# Debugger.net
KiCad netlist of a schematic drawn in Altium Designer
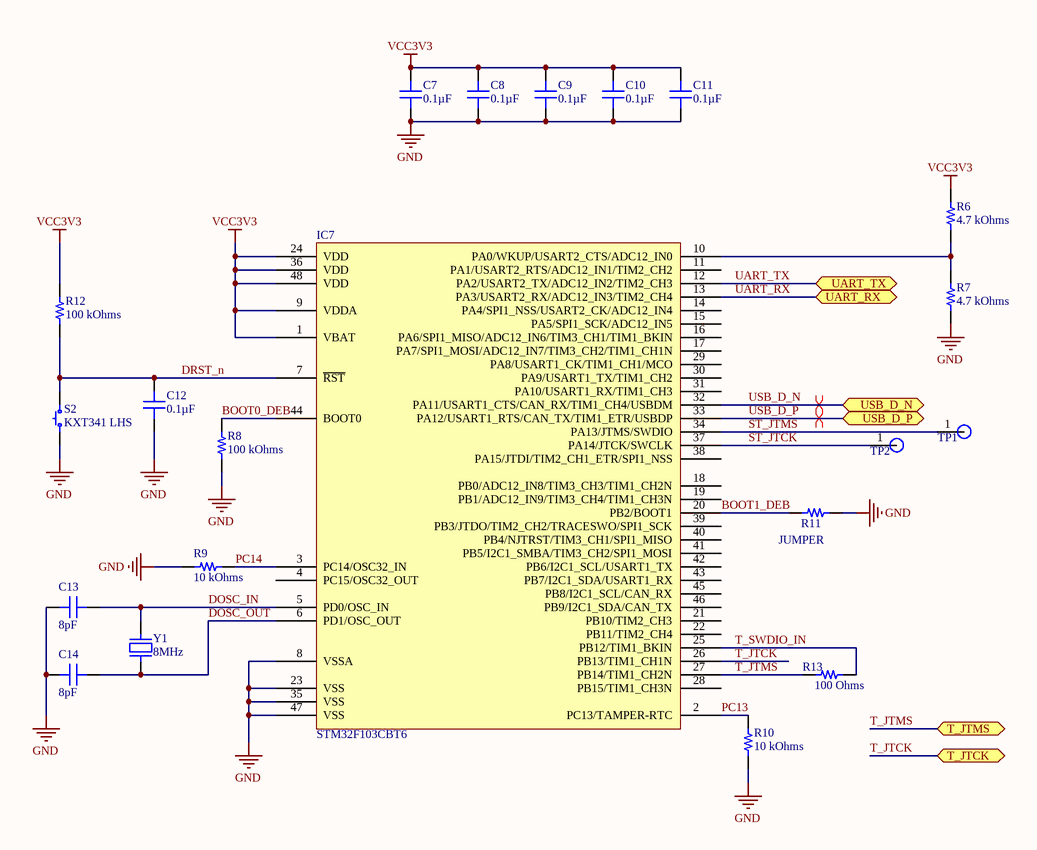
[diagram p0: Debugger.SchDoc]

(export (version "E")
  (design (tool "Eeschema 10.0.6"))
  (components
    (comp (ref "C7")
      (value "0.1µF")
      (footprint "CAP 0201_0603")
      (description "CAP CER 0.1UF 16V X5R 0201")
      (fields (field (name "PART NUMBER") "EMK063BJ104KP-F") (field (name "MANUFACTURER") "Taiyo Yuden"))
      (libsource (lib "Celestial") (part "Capacitor"))
    )
    (comp (ref "C8")
      (value "0.1µF")
      (footprint "CAP 0201_0603")
      (description "CAP CER 0.1UF 16V X5R 0201")
      (fields (field (name "PART NUMBER") "EMK063BJ104KP-F") (field (name "MANUFACTURER") "Taiyo Yuden"))
      (libsource (lib "Celestial") (part "Capacitor"))
    )
    (comp (ref "C9")
      (value "0.1µF")
      (footprint "CAP 0201_0603")
      (description "CAP CER 0.1UF 16V X5R 0201")
      (fields (field (name "PART NUMBER") "EMK063BJ104KP-F") (field (name "MANUFACTURER") "Taiyo Yuden"))
      (libsource (lib "Celestial") (part "Capacitor"))
    )
    (comp (ref "C10")
      (value "0.1µF")
      (footprint "CAP 0201_0603")
      (description "CAP CER 0.1UF 16V X5R 0201")
      (fields (field (name "PART NUMBER") "EMK063BJ104KP-F") (field (name "MANUFACTURER") "Taiyo Yuden"))
      (libsource (lib "Celestial") (part "Capacitor"))
    )
    (comp (ref "C11")
      (value "0.1µF")
      (footprint "CAP 0201_0603")
      (description "CAP CER 0.1UF 16V X5R 0201")
      (fields (field (name "PART NUMBER") "EMK063BJ104KP-F") (field (name "MANUFACTURER") "Taiyo Yuden"))
      (libsource (lib "Celestial") (part "Capacitor"))
    )
    (comp (ref "C12")
      (value "0.1µF")
      (footprint "CAP 0201_0603")
      (description "CAP CER 0.1UF 16V X5R 0201")
      (fields (field (name "PART NUMBER") "EMK063BJ104KP-F") (field (name "MANUFACTURER") "Taiyo Yuden"))
      (libsource (lib "Celestial") (part "Capacitor"))
    )
    (comp (ref "C13")
      (value "8pF")
      (footprint "CAP 0402_1005")
      (description "CAP CER 8PF 50V NP0 0402")
      (fields
        (field (name "PART NUMBER") "C1005NP01H080D050BA")
        (field (name "MANUFACTURER") "TDK Corporation")
      )
      (libsource (lib "Celestial") (part "Capacitor"))
    )
    (comp (ref "C14")
      (value "8pF")
      (footprint "CAP 0402_1005")
      (description "CAP CER 8PF 50V NP0 0402")
      (fields
        (field (name "PART NUMBER") "C1005NP01H080D050BA")
        (field (name "MANUFACTURER") "TDK Corporation")
      )
      (libsource (lib "Celestial") (part "Capacitor"))
    )
    (comp (ref "IC7")
      (value "STM32F103CBT6")
      (footprint "ST LQFP-48 7X7MM")
      (description "IC MCU 32BIT 128KB FLASH 48LQFP")
      (fields (field (name "MANUFACTURER") "STMicroelectronics"))
      (libsource (lib "Celestial") (part "ST STM32F103 48PIN"))
    )
    (comp (ref "R6")
      (value "4.7 kOhms")
      (footprint "RES 0201_0603")
      (description "RES SMD 4.7K OHM 1% 1/20W 0201")
      (fields (field (name "PART NUMBER") "CRCW02014K70FKED") (field (name "MANUFACTURER") "Vishay Dale"))
      (libsource (lib "Celestial") (part "Resistor"))
    )
    (comp (ref "R7")
      (value "4.7 kOhms")
      (footprint "RES 0201_0603")
      (description "RES SMD 4.7K OHM 1% 1/20W 0201")
      (fields (field (name "PART NUMBER") "CRCW02014K70FKED") (field (name "MANUFACTURER") "Vishay Dale"))
      (libsource (lib "Celestial") (part "Resistor"))
    )
    (comp (ref "R8")
      (value "100 kOhms")
      (footprint "RES 0402_1005")
      (description "RES SMD 100K OHM 1% 1/16W 0402")
      (fields (field (name "PART NUMBER") "AC0402FR-07100KL") (field (name "MANUFACTURER") "Yageo"))
      (libsource (lib "Celestial") (part "Resistor"))
    )
    (comp (ref "R9")
      (value "10 kOhms")
      (footprint "RES 0201_0603")
      (description "RES SMD 10K OHM 1% 1/20W 0201")
      (fields (field (name "PART NUMBER") "CRCW020110K0FKED") (field (name "MANUFACTURER") "Vishay Dale"))
      (libsource (lib "Celestial") (part "Resistor"))
    )
    (comp (ref "R10")
      (value "10 kOhms")
      (footprint "RES 0201_0603")
      (description "RES SMD 10K OHM 1% 1/20W 0201")
      (fields (field (name "PART NUMBER") "CRCW020110K0FKED") (field (name "MANUFACTURER") "Vishay Dale"))
      (libsource (lib "Celestial") (part "Resistor"))
    )
    (comp (ref "R11")
      (value "JUMPER")
      (footprint "RES 0402_1005")
      (description "0402 JUMPER ON TAPE AND REEL")
      (fields (field (name "PART NUMBER") "5113") (field (name "MANUFACTURER") "Keystone Electronics"))
      (libsource (lib "Celestial") (part "Resistor"))
    )
    (comp (ref "R12")
      (value "100 kOhms")
      (footprint "RES 0201_0603")
      (description "RES SMD 100K OHM 1% 1/20W 0201")
      (fields
        (field (name "PART NUMBER") "CRG0201F100K")
        (field (name "MANUFACTURER") "TE Connectivity Passive Product")
      )
      (libsource (lib "Celestial") (part "Resistor"))
    )
    (comp (ref "R13")
      (value "100 Ohms")
      (footprint "RES 0201_0603")
      (description "RES SMD 100 OHM 1% 1/20W 0201")
      (fields (field (name "PART NUMBER") "CRCW0201100RFKED") (field (name "MANUFACTURER") "Vishay Dale"))
      (libsource (lib "Celestial") (part "Resistor"))
    )
    (comp (ref "S2")
      (value "KXT341 LHS")
      (footprint "C&K KXT3")
      (description "SWITCH TACTILE SPST-NO 0.02A 15V")
      (fields (field (name "MANUFACTURER") "C&K"))
      (libsource (lib "Celestial") (part "SPST-NO 2 PIN"))
    )
    (comp (ref "TP1") (value "Test Point") (footprint "ethan:TP1") (libsource (lib "ethan") (part "TP1")))
    (comp (ref "TP2") (value "Test Point") (footprint "ethan:TP1") (libsource (lib "ethan") (part "TP1")))
    (comp (ref "Y1")
      (value "8MHz")
      (footprint "NDK NX3225GD")
      (description "CRYSTAL 8.0000MHZ 8PF SMD")
      (fields
        (field (name "PART NUMBER") "NX3225GD-8MHZ-STD-CRA-3")
        (field (name "MANUFACTURER") "NDK America, Inc.")
      )
      (libsource (lib "Celestial") (part "NDK NX3225GD"))
    )
  )
  (nets
    (net (code "1") (name "/BOOT0_DEB") (class "Default")
      (node (ref "IC7") (pin "44") (pinfunction "BOOT0_44") (pintype "passive"))
      (node (ref "R8") (pin "2") (pinfunction "2_2") (pintype "passive"))
    )
    (net (code "2") (name "/BOOT1_DEB") (class "Default")
      (node (ref "IC7") (pin "20") (pinfunction "PB2/BOOT1_20") (pintype "passive"))
      (node (ref "R11") (pin "2") (pinfunction "2_2") (pintype "passive"))
    )
    (net (code "3") (name "/DOSC_IN") (class "Default")
      (node (ref "C13") (pin "2") (pinfunction "2_2") (pintype "passive"))
      (node (ref "IC7") (pin "5") (pinfunction "PD0/OSC_IN_5") (pintype "passive"))
      (node (ref "Y1") (pin "2") (pinfunction "2_2") (pintype "passive"))
    )
    (net (code "4") (name "/DOSC_OUT") (class "Default")
      (node (ref "C14") (pin "2") (pinfunction "2_2") (pintype "passive"))
      (node (ref "IC7") (pin "6") (pinfunction "PD1/OSC_OUT_6") (pintype "passive"))
      (node (ref "Y1") (pin "1") (pinfunction "1_1") (pintype "passive"))
    )
    (net (code "5") (name "/DRST_n") (class "Default")
      (node (ref "C12") (pin "2") (pinfunction "2_2") (pintype "passive"))
      (node (ref "IC7") (pin "7") (pinfunction "~{RST}_7") (pintype "passive"))
      (node (ref "R12") (pin "1") (pinfunction "1_1") (pintype "passive"))
      (node (ref "S2") (pin "2") (pinfunction "2_2") (pintype "passive"))
    )
    (net (code "6") (name "/PC13") (class "Default")
      (node (ref "IC7") (pin "2") (pinfunction "PC13/TAMPER-RTC_2") (pintype "passive"))
      (node (ref "R10") (pin "2") (pinfunction "2_2") (pintype "passive"))
    )
    (net (code "7") (name "/PC14") (class "Default")
      (node (ref "IC7") (pin "3") (pinfunction "PC14/OSC32_IN_3") (pintype "passive"))
      (node (ref "R9") (pin "1") (pinfunction "1_1") (pintype "passive"))
    )
    (net (code "8") (name "/ST_JTCK") (class "Default")
      (node (ref "IC7") (pin "37") (pinfunction "PA14/JTCK/SWCLK_37") (pintype "passive"))
      (node (ref "TP2") (pin "1") (pinfunction "1_1") (pintype "passive"))
    )
    (net (code "9") (name "/ST_JTMS") (class "Default")
      (node (ref "IC7") (pin "34") (pinfunction "PA13/JTMS/SWDIO_34") (pintype "passive"))
      (node (ref "TP1") (pin "1") (pinfunction "1_1") (pintype "passive"))
    )
    (net (code "10") (name "/T_JTCK") (class "Default")
      (node (ref "IC7") (pin "26") (pinfunction "PB13/TIM1_CH1N_26") (pintype "passive"))
    )
    (net (code "11") (name "/T_JTMS") (class "Default")
      (node (ref "IC7") (pin "27") (pinfunction "PB14/TIM1_CH2N_27") (pintype "passive"))
      (node (ref "R13") (pin "1") (pinfunction "1_1") (pintype "passive"))
    )
    (net (code "12") (name "/T_SWDIO_IN") (class "Default")
      (node (ref "IC7") (pin "25") (pinfunction "PB12/TIM1_BKIN_25") (pintype "passive"))
      (node (ref "R13") (pin "2") (pinfunction "2_2") (pintype "passive"))
    )
    (net (code "13") (name "/UART_RX") (class "Default")
      (node (ref "IC7") (pin "13") (pinfunction "PA3/USART2_RX/ADC12_IN3/TIM2_CH4_13") (pintype "passive"))
    )
    (net (code "14") (name "/UART_TX") (class "Default")
      (node (ref "IC7") (pin "12") (pinfunction "PA2/USART2_TX/ADC12_IN2/TIM2_CH3_12") (pintype "passive"))
    )
    (net (code "15") (name "/USB_D_N") (class "Default")
      (node (ref "IC7") (pin "32") (pinfunction "PA11/USART1_CTS/CAN_RX/TIM1_CH4/USBDM_32") (pintype "passive"))
    )
    (net (code "16") (name "/USB_D_P") (class "Default")
      (node (ref "IC7") (pin "33") (pinfunction "PA12/USART1_RTS/CAN_TX/TIM1_ETR/USBDP_33") (pintype "passive"))
    )
    (net (code "17") (name "GND") (class "Default")
      (node (ref "C10") (pin "1") (pinfunction "1_1") (pintype "passive"))
      (node (ref "C11") (pin "1") (pinfunction "1_1") (pintype "passive"))
      (node (ref "C12") (pin "1") (pinfunction "1_1") (pintype "passive"))
      (node (ref "C13") (pin "1") (pinfunction "1_1") (pintype "passive"))
      (node (ref "C14") (pin "1") (pinfunction "1_1") (pintype "passive"))
      (node (ref "C7") (pin "1") (pinfunction "1_1") (pintype "passive"))
      (node (ref "C8") (pin "1") (pinfunction "1_1") (pintype "passive"))
      (node (ref "C9") (pin "1") (pinfunction "1_1") (pintype "passive"))
      (node (ref "IC7") (pin "23") (pinfunction "VSS_23") (pintype "passive"))
      (node (ref "IC7") (pin "35") (pinfunction "VSS_35") (pintype "passive"))
      (node (ref "IC7") (pin "47") (pinfunction "VSS_47") (pintype "passive"))
      (node (ref "IC7") (pin "8") (pinfunction "VSSA_8") (pintype "passive"))
      (node (ref "R10") (pin "1") (pinfunction "1_1") (pintype "passive"))
      (node (ref "R11") (pin "1") (pinfunction "1_1") (pintype "passive"))
      (node (ref "R7") (pin "1") (pinfunction "1_1") (pintype "passive"))
      (node (ref "R8") (pin "1") (pinfunction "1_1") (pintype "passive"))
      (node (ref "R9") (pin "2") (pinfunction "2_2") (pintype "passive"))
      (node (ref "S2") (pin "1") (pinfunction "1_1") (pintype "passive"))
    )
    (net (code "18") (name "Net-(IC7-PA0{slash}WKUP{slash}USART2_CTS{slash}ADC12_IN0)") (class "Default")
      (node (ref "IC7") (pin "10") (pinfunction "PA0/WKUP/USART2_CTS/ADC12_IN0_10") (pintype "passive"))
      (node (ref "R6") (pin "1") (pinfunction "1_1") (pintype "passive"))
      (node (ref "R7") (pin "2") (pinfunction "2_2") (pintype "passive"))
    )
    (net (code "19") (name "VCC3V3") (class "Default")
      (node (ref "C10") (pin "2") (pinfunction "2_2") (pintype "passive"))
      (node (ref "C11") (pin "2") (pinfunction "2_2") (pintype "passive"))
      (node (ref "C7") (pin "2") (pinfunction "2_2") (pintype "passive"))
      (node (ref "C8") (pin "2") (pinfunction "2_2") (pintype "passive"))
      (node (ref "C9") (pin "2") (pinfunction "2_2") (pintype "passive"))
      (node (ref "IC7") (pin "1") (pinfunction "VBAT_1") (pintype "passive"))
      (node (ref "IC7") (pin "24") (pinfunction "VDD_24") (pintype "passive"))
      (node (ref "IC7") (pin "36") (pinfunction "VDD_36") (pintype "passive"))
      (node (ref "IC7") (pin "48") (pinfunction "VDD_48") (pintype "passive"))
      (node (ref "IC7") (pin "9") (pinfunction "VDDA_9") (pintype "passive"))
      (node (ref "R12") (pin "2") (pinfunction "2_2") (pintype "passive"))
      (node (ref "R6") (pin "2") (pinfunction "2_2") (pintype "passive"))
    )
    (net (code "20") (name "unconnected-(IC7-PA1{slash}USART2_RTS{slash}ADC12_IN1{slash}TIM2_CH2-Pad11)") (class "Default")
      (node (ref "IC7") (pin "11") (pinfunction "PA1/USART2_RTS/ADC12_IN1/TIM2_CH2_11") (pintype "passive"))
    )
    (net (code "21") (name "unconnected-(IC7-PA4{slash}SPI1_NSS{slash}USART2_CK{slash}ADC12_IN4-Pad14)") (class "Default")
      (node (ref "IC7") (pin "14") (pinfunction "PA4/SPI1_NSS/USART2_CK/ADC12_IN4_14") (pintype "passive"))
    )
    (net (code "22") (name "unconnected-(IC7-PA5{slash}SPI1_SCK{slash}ADC12_IN5-Pad15)") (class "Default")
      (node (ref "IC7") (pin "15") (pinfunction "PA5/SPI1_SCK/ADC12_IN5_15") (pintype "passive"))
    )
    (net (code "23") (name "unconnected-(IC7-PA6{slash}SPI1_MISO{slash}ADC12_IN6{slash}TIM3_CH1{slash}TIM1_BKIN-Pad16)") (class "Default")
      (node (ref "IC7") (pin "16") (pinfunction "PA6/SPI1_MISO/ADC12_IN6/TIM3_CH1/TIM1_BKIN_16") (pintype "passive"))
    )
    (net (code "24") (name "unconnected-(IC7-PA7{slash}SPI1_MOSI{slash}ADC12_IN7{slash}TIM3_CH2{slash}TIM1_CH1N-Pad17)") (class "Default")
      (node (ref "IC7") (pin "17") (pinfunction "PA7/SPI1_MOSI/ADC12_IN7/TIM3_CH2/TIM1_CH1N_17") (pintype "passive"))
    )
    (net (code "25") (name "unconnected-(IC7-PA8{slash}USART1_CK{slash}TIM1_CH1{slash}MCO-Pad29)") (class "Default")
      (node (ref "IC7") (pin "29") (pinfunction "PA8/USART1_CK/TIM1_CH1/MCO_29") (pintype "passive"))
    )
    (net (code "26") (name "unconnected-(IC7-PA9{slash}USART1_TX{slash}TIM1_CH2-Pad30)") (class "Default")
      (node (ref "IC7") (pin "30") (pinfunction "PA9/USART1_TX/TIM1_CH2_30") (pintype "passive"))
    )
    (net (code "27") (name "unconnected-(IC7-PA10{slash}USART1_RX{slash}TIM1_CH3-Pad31)") (class "Default")
      (node (ref "IC7") (pin "31") (pinfunction "PA10/USART1_RX/TIM1_CH3_31") (pintype "passive"))
    )
    (net (code "28") (name "unconnected-(IC7-PA15{slash}JTDI{slash}TIM2_CH1_ETR{slash}SPI1_NSS-Pad38)") (class "Default")
      (node (ref "IC7") (pin "38") (pinfunction "PA15/JTDI/TIM2_CH1_ETR/SPI1_NSS_38") (pintype "passive"))
    )
    (net (code "29") (name "unconnected-(IC7-PB0{slash}ADC12_IN8{slash}TIM3_CH3{slash}TIM1_CH2N-Pad18)") (class "Default")
      (node (ref "IC7") (pin "18") (pinfunction "PB0/ADC12_IN8/TIM3_CH3/TIM1_CH2N_18") (pintype "passive"))
    )
    (net (code "30") (name "unconnected-(IC7-PB1{slash}ADC12_IN9{slash}TIM3_CH4{slash}TIM1_CH3N-Pad19)") (class "Default")
      (node (ref "IC7") (pin "19") (pinfunction "PB1/ADC12_IN9/TIM3_CH4/TIM1_CH3N_19") (pintype "passive"))
    )
    (net (code "31") (name "unconnected-(IC7-PB3{slash}JTDO{slash}TIM2_CH2{slash}TRACESWO{slash}SPI1_SCK-Pad39)") (class "Default")
      (node (ref "IC7") (pin "39") (pinfunction "PB3/JTDO/TIM2_CH2/TRACESWO/SPI1_SCK_39") (pintype "passive"))
    )
    (net (code "32") (name "unconnected-(IC7-PB4{slash}NJTRST{slash}TIM3_CH1{slash}SPI1_MISO-Pad40)") (class "Default")
      (node (ref "IC7") (pin "40") (pinfunction "PB4/NJTRST/TIM3_CH1/SPI1_MISO_40") (pintype "passive"))
    )
    (net (code "33") (name "unconnected-(IC7-PB5{slash}I2C1_SMBA{slash}TIM3_CH2{slash}SPI1_MOSI-Pad41)") (class "Default")
      (node (ref "IC7") (pin "41") (pinfunction "PB5/I2C1_SMBA/TIM3_CH2/SPI1_MOSI_41") (pintype "passive"))
    )
    (net (code "34") (name "unconnected-(IC7-PB6{slash}I2C1_SCL{slash}USART1_TX-Pad42)") (class "Default")
      (node (ref "IC7") (pin "42") (pinfunction "PB6/I2C1_SCL/USART1_TX_42") (pintype "passive"))
    )
    (net (code "35") (name "unconnected-(IC7-PB7{slash}I2C1_SDA{slash}USART1_RX-Pad43)") (class "Default")
      (node (ref "IC7") (pin "43") (pinfunction "PB7/I2C1_SDA/USART1_RX_43") (pintype "passive"))
    )
    (net (code "36") (name "unconnected-(IC7-PB8{slash}I2C1_SCL{slash}CAN_RX-Pad45)") (class "Default")
      (node (ref "IC7") (pin "45") (pinfunction "PB8/I2C1_SCL/CAN_RX_45") (pintype "passive"))
    )
    (net (code "37") (name "unconnected-(IC7-PB9{slash}I2C1_SDA{slash}CAN_TX-Pad46)") (class "Default")
      (node (ref "IC7") (pin "46") (pinfunction "PB9/I2C1_SDA/CAN_TX_46") (pintype "passive"))
    )
    (net (code "38") (name "unconnected-(IC7-PB10{slash}TIM2_CH3-Pad21)") (class "Default")
      (node (ref "IC7") (pin "21") (pinfunction "PB10/TIM2_CH3_21") (pintype "passive"))
    )
    (net (code "39") (name "unconnected-(IC7-PB11{slash}TIM2_CH4-Pad22)") (class "Default")
      (node (ref "IC7") (pin "22") (pinfunction "PB11/TIM2_CH4_22") (pintype "passive"))
    )
    (net (code "40") (name "unconnected-(IC7-PB15{slash}TIM1_CH3N-Pad28)") (class "Default")
      (node (ref "IC7") (pin "28") (pinfunction "PB15/TIM1_CH3N_28") (pintype "passive"))
    )
    (net (code "41") (name "unconnected-(IC7-PC15{slash}OSC32_OUT-Pad4)") (class "Default")
      (node (ref "IC7") (pin "4") (pinfunction "PC15/OSC32_OUT_4") (pintype "passive"))
    )
  )
)
